# Power.net
KiCad netlist of a schematic drawn in Altium Designer
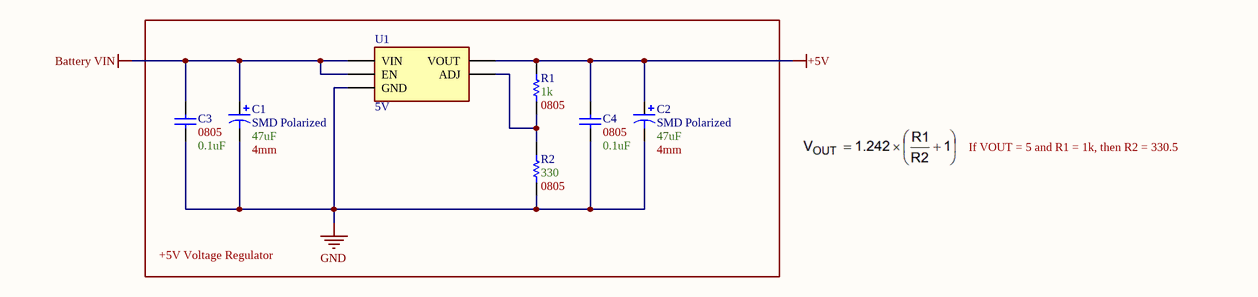
[diagram p0: Power.SchDoc]

(export (version "E")
  (design (tool "Eeschema 10.0.6"))
  (components
    (comp (ref "C1")
      (value "SMD Polarized")
      (footprint "[Cap] SMD Polarized, 4mm")
      (fields (field (name "CAPACITANCE") "47uF") (field (name "DIAMETER") "4mm"))
      (libsource (lib "RADM Components") (part "[Cap] SMD Polarized"))
    )
    (comp (ref "C2")
      (value "SMD Polarized")
      (footprint "[Cap] SMD Polarized, 4mm")
      (fields (field (name "CAPACITANCE") "47uF") (field (name "DIAMETER") "4mm"))
      (libsource (lib "RADM Components") (part "[Cap] SMD Polarized"))
    )
    (comp (ref "C3")
      (value "SMD Nonpolarized")
      (footprint "[Cap] SMD 0805")
      (fields (field (name "SIZE PACKAGE") "0805") (field (name "CAPACITANCE") "0.1uF"))
      (libsource (lib "RADM Components") (part "[Cap] SMD Nonpolarized"))
    )
    (comp (ref "C4")
      (value "SMD Nonpolarized")
      (footprint "[Cap] SMD 0805")
      (fields (field (name "SIZE PACKAGE") "0805") (field (name "CAPACITANCE") "0.1uF"))
      (libsource (lib "RADM Components") (part "[Cap] SMD Nonpolarized"))
    )
    (comp (ref "R1")
      (value "[Res] SMD Resistor")
      (footprint "[Res] SMD 0805")
      (fields (field (name "RESISTANCE") "1k") (field (name "SIZE PACKAGE") "0805"))
      (libsource (lib "RADM Components") (part "[Res] SMD Resistor"))
    )
    (comp (ref "R2")
      (value "[Res] SMD Resistor")
      (footprint "[Res] SMD 0805")
      (fields (field (name "RESISTANCE") "330") (field (name "SIZE PACKAGE") "0805"))
      (libsource (lib "RADM Components") (part "[Res] SMD Resistor"))
    )
    (comp (ref "U1")
      (value "5V")
      (footprint "[Reg] Variable Voltage Regulator")
      (description "MIC29302WT")
      (libsource (lib "RADM Components") (part "[Reg] Variable Voltage Regulator"))
    )
  )
  (nets
    (net (code "1") (name "+5V") (class "Default")
      (node (ref "C2") (pin "1") (pinfunction "1_1") (pintype "passive"))
      (node (ref "C4") (pin "2") (pinfunction "2_2") (pintype "passive"))
      (node (ref "R1") (pin "2") (pinfunction "2_2") (pintype "passive"))
      (node (ref "U1") (pin "4") (pinfunction "VOUT_4") (pintype "power_in"))
    )
    (net (code "2") (name "Battery VIN") (class "Default")
      (node (ref "C1") (pin "1") (pinfunction "1_1") (pintype "passive"))
      (node (ref "C3") (pin "2") (pinfunction "2_2") (pintype "passive"))
      (node (ref "U1") (pin "1") (pinfunction "EN_1") (pintype "power_in"))
      (node (ref "U1") (pin "2") (pinfunction "VIN_2") (pintype "power_in"))
    )
    (net (code "3") (name "GND") (class "Default")
      (node (ref "C1") (pin "2") (pinfunction "2_2") (pintype "passive"))
      (node (ref "C2") (pin "2") (pinfunction "2_2") (pintype "passive"))
      (node (ref "C3") (pin "1") (pinfunction "1_1") (pintype "passive"))
      (node (ref "C4") (pin "1") (pinfunction "1_1") (pintype "passive"))
      (node (ref "R2") (pin "1") (pinfunction "1_1") (pintype "passive"))
      (node (ref "U1") (pin "3") (pinfunction "GND_3") (pintype "power_in"))
    )
    (net (code "4") (name "Net-(U1-ADJ)") (class "Default")
      (node (ref "R1") (pin "1") (pinfunction "1_1") (pintype "passive"))
      (node (ref "R2") (pin "2") (pinfunction "2_2") (pintype "passive"))
      (node (ref "U1") (pin "5") (pinfunction "ADJ_5") (pintype "power_in"))
    )
  )
)
